# POE_PD_3_P-Schalter.net
KiCad netlist of a schematic drawn in EAGLE
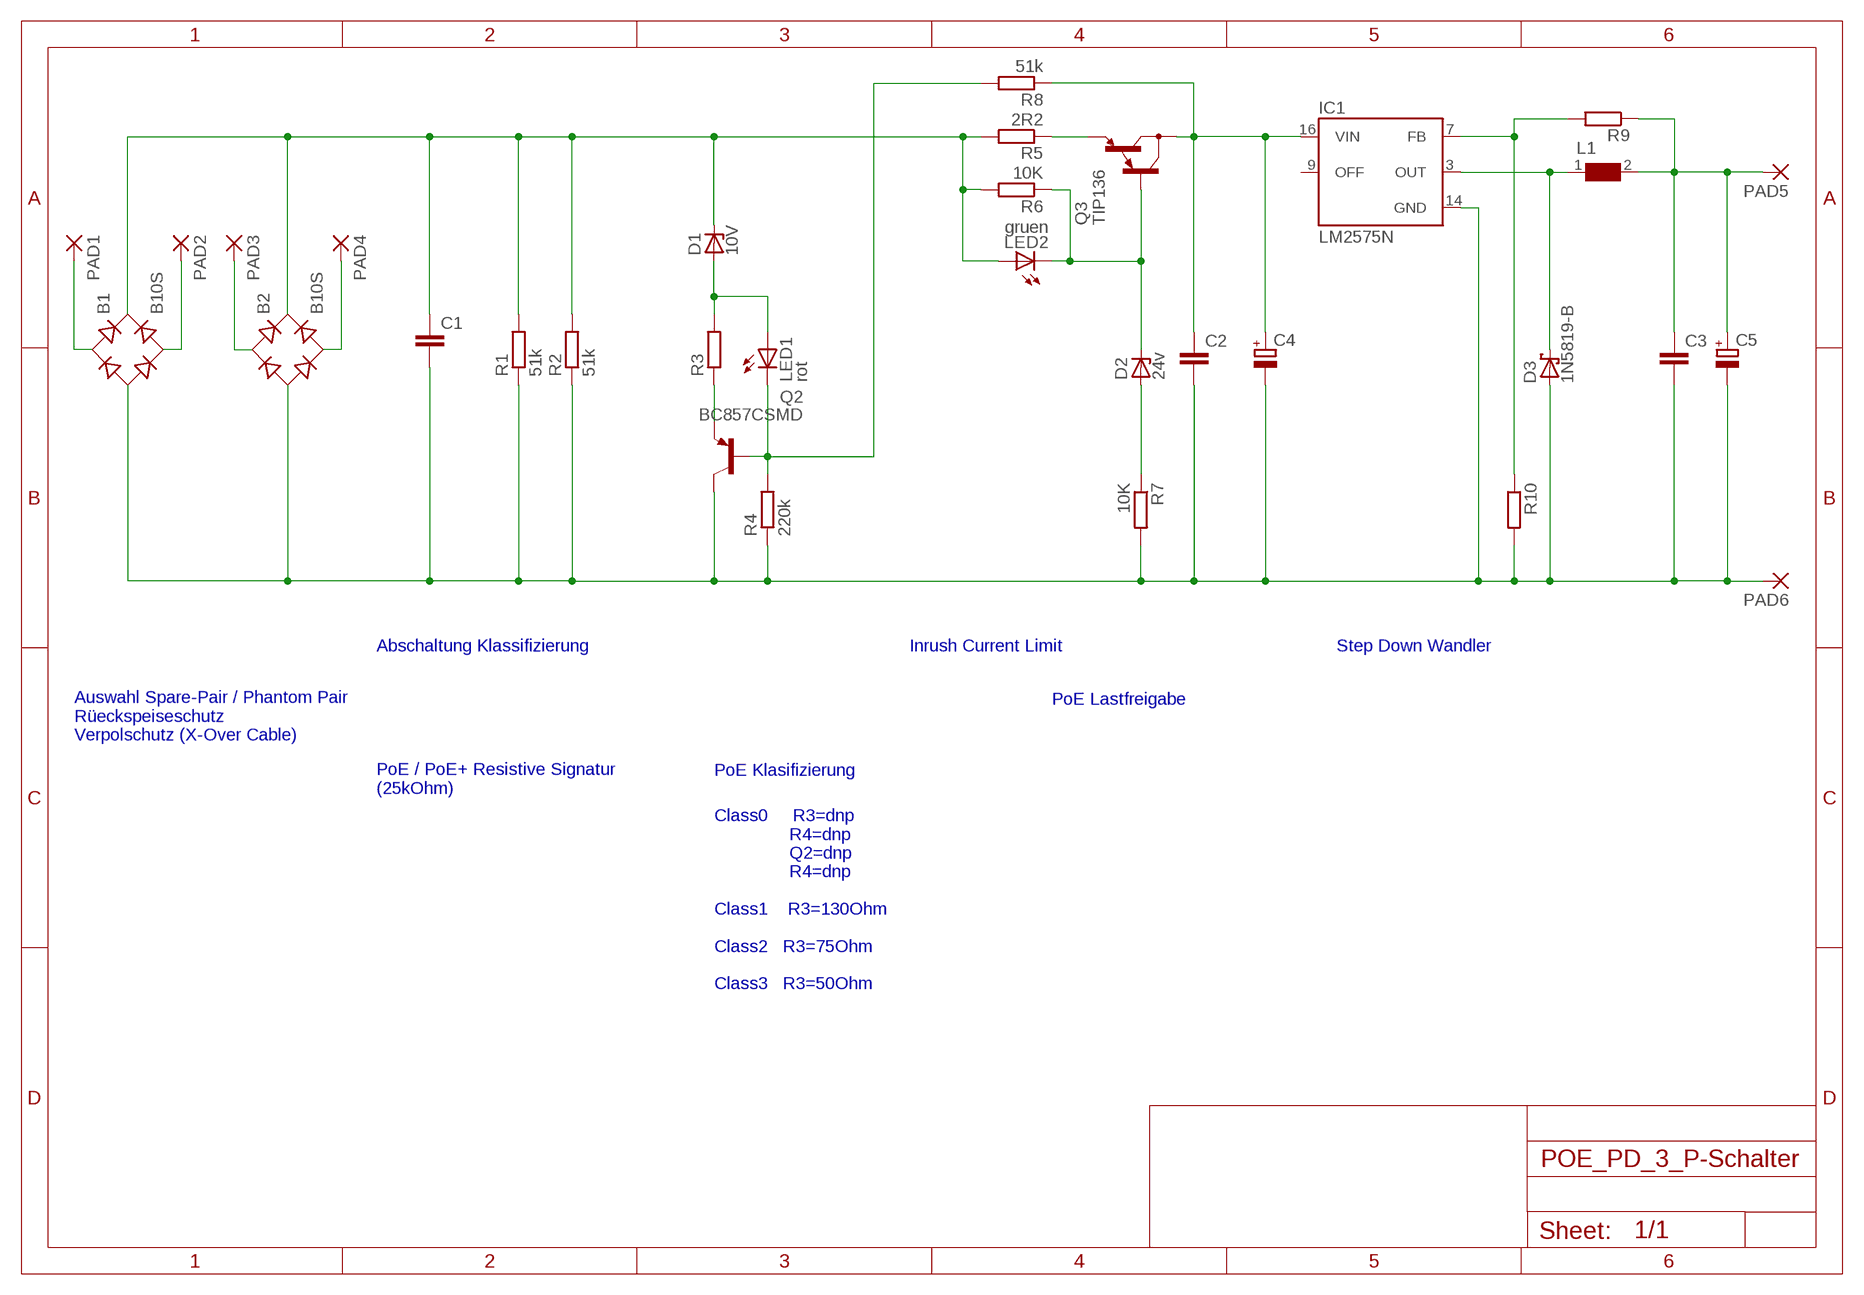
[diagram p0: schematic, sheet 1]

(export (version "E")
  (design (tool "Eeschema 10.0.6"))
  (components
    (comp (ref "B1")
      (value "B10S")
      (footprint "eagle-import:MBS")
      (libsource (lib "eagle-import") (part "BS10"))
    )
    (comp (ref "B2")
      (value "B10S")
      (footprint "eagle-import:MBS")
      (libsource (lib "eagle-import") (part "BS10"))
    )
    (comp (ref "C1")
      (value "C-EUC0805")
      (footprint "eagle-import:C0805")
      (libsource (lib "eagle-import") (part "C-EUC0805"))
    )
    (comp (ref "C2")
      (value "C-EUC0805")
      (footprint "eagle-import:C0805")
      (libsource (lib "eagle-import") (part "C-EUC0805"))
    )
    (comp (ref "C3")
      (value "C-EUC0805")
      (footprint "eagle-import:C0805")
      (libsource (lib "eagle-import") (part "C-EUC0805"))
    )
    (comp (ref "C4")
      (value "CPOL-EU153CLV-0605")
      (footprint "eagle-import:153CLV-0605")
      (libsource (lib "eagle-import") (part "CPOL-EU153CLV-0605"))
    )
    (comp (ref "C5")
      (value "CPOL-EU153CLV-0605")
      (footprint "eagle-import:153CLV-0605")
      (libsource (lib "eagle-import") (part "CPOL-EU153CLV-0605"))
    )
    (comp (ref "D1")
      (value "10V")
      (footprint "eagle-import:SOT23")
      (libsource (lib "eagle-import") (part "ZENER-DIODESOT23"))
    )
    (comp (ref "D2")
      (value "24v")
      (footprint "eagle-import:SOT23")
      (libsource (lib "eagle-import") (part "ZENER-DIODESOT23"))
    )
    (comp (ref "D3")
      (value "1N5819-B")
      (footprint "eagle-import:DO41-7.6")
      (libsource (lib "eagle-import") (part "1N5819-B"))
    )
    (comp (ref "IC1")
      (value "LM2575N")
      (footprint "eagle-import:DIL16")
      (libsource (lib "eagle-import") (part "LM2575N"))
    )
    (comp (ref "L1")
      (value "WE-PD2_S")
      (footprint "eagle-import:WE-PD2_S")
      (libsource (lib "eagle-import") (part "WE-PD2_S"))
    )
    (comp (ref "LED1")
      (value "rot")
      (footprint "eagle-import:CHIP-LED0805")
      (libsource (lib "eagle-import") (part "LEDCHIP-LED0805"))
    )
    (comp (ref "LED2")
      (value "gruen")
      (footprint "eagle-import:CHIP-LED0805")
      (libsource (lib "eagle-import") (part "LEDCHIP-LED0805"))
    )
    (comp (ref "PAD1")
      (value "2,15/1,0")
      (footprint "eagle-import:2,15_1,0")
      (libsource (lib "eagle-import") (part "2,15/1,0"))
    )
    (comp (ref "PAD2")
      (value "2,15/1,0")
      (footprint "eagle-import:2,15_1,0")
      (libsource (lib "eagle-import") (part "2,15/1,0"))
    )
    (comp (ref "PAD3")
      (value "2,15/1,0")
      (footprint "eagle-import:2,15_1,0")
      (libsource (lib "eagle-import") (part "2,15/1,0"))
    )
    (comp (ref "PAD4")
      (value "2,15/1,0")
      (footprint "eagle-import:2,15_1,0")
      (libsource (lib "eagle-import") (part "2,15/1,0"))
    )
    (comp (ref "PAD5")
      (value "2,15/1,0")
      (footprint "eagle-import:2,15_1,0")
      (libsource (lib "eagle-import") (part "2,15/1,0"))
    )
    (comp (ref "PAD6")
      (value "2,15/1,0")
      (footprint "eagle-import:2,15_1,0")
      (libsource (lib "eagle-import") (part "2,15/1,0"))
    )
    (comp (ref "Q2")
      (value "BC857CSMD")
      (footprint "eagle-import:SOT23-BEC")
      (libsource (lib "eagle-import") (part "BC857SMDC"))
    )
    (comp (ref "Q3")
      (value "TIP136")
      (footprint "eagle-import:TO220")
      (libsource (lib "eagle-import") (part "TIP136"))
    )
    (comp (ref "R1")
      (value "51k")
      (footprint "eagle-import:R0603")
      (libsource (lib "eagle-import") (part "R-EU_R0603"))
    )
    (comp (ref "R2")
      (value "51k")
      (footprint "eagle-import:R0603")
      (libsource (lib "eagle-import") (part "R-EU_R0603"))
    )
    (comp (ref "R3")
      (value "R-EU_R0603")
      (footprint "eagle-import:R0603")
      (libsource (lib "eagle-import") (part "R-EU_R0603"))
    )
    (comp (ref "R4")
      (value "220k")
      (footprint "eagle-import:R0603")
      (libsource (lib "eagle-import") (part "R-EU_R0603"))
    )
    (comp (ref "R5")
      (value "2R2")
      (footprint "eagle-import:R0603")
      (libsource (lib "eagle-import") (part "R-EU_R0603"))
    )
    (comp (ref "R6")
      (value "10K")
      (footprint "eagle-import:R0603")
      (libsource (lib "eagle-import") (part "R-EU_R0603"))
    )
    (comp (ref "R7")
      (value "10K")
      (footprint "eagle-import:R0603")
      (libsource (lib "eagle-import") (part "R-EU_R0603"))
    )
    (comp (ref "R8")
      (value "51k")
      (footprint "eagle-import:R0603")
      (libsource (lib "eagle-import") (part "R-EU_R0603"))
    )
    (comp (ref "R9")
      (value "R-EU_R0603")
      (footprint "eagle-import:R0603")
      (libsource (lib "eagle-import") (part "R-EU_R0603"))
    )
    (comp (ref "R10")
      (value "R-EU_R0603")
      (footprint "eagle-import:R0603")
      (libsource (lib "eagle-import") (part "R-EU_R0603"))
    )
  )
  (nets
    (net (code "1") (name "Net-(D1-A)") (class "Default")
      (node (ref "D1") (pin "1") (pinfunction "A_1") (pintype "passive"))
      (node (ref "LED1") (pin "A") (pinfunction "A_A") (pintype "passive"))
      (node (ref "R3") (pin "2") (pinfunction "2_2") (pintype "passive"))
    )
    (net (code "2") (name "Net-(D1-C)") (class "Default")
      (node (ref "B1") (pin "+") (pinfunction "+_+") (pintype "passive"))
      (node (ref "B2") (pin "+") (pinfunction "+_+") (pintype "passive"))
      (node (ref "C1") (pin "1") (pinfunction "1_1") (pintype "passive"))
      (node (ref "D1") (pin "3") (pinfunction "C_3") (pintype "passive"))
      (node (ref "LED2") (pin "A") (pinfunction "A_A") (pintype "passive"))
      (node (ref "R1") (pin "2") (pinfunction "2_2") (pintype "passive"))
      (node (ref "R2") (pin "2") (pinfunction "2_2") (pintype "passive"))
      (node (ref "R5") (pin "2") (pinfunction "2_2") (pintype "passive"))
      (node (ref "R6") (pin "2") (pinfunction "2_2") (pintype "passive"))
    )
    (net (code "3") (name "Net-(D2-A)") (class "Default")
      (node (ref "D2") (pin "1") (pinfunction "A_1") (pintype "passive"))
      (node (ref "R7") (pin "1") (pinfunction "1_1") (pintype "passive"))
    )
    (net (code "4") (name "Net-(D2-C)") (class "Default")
      (node (ref "D2") (pin "3") (pinfunction "C_3") (pintype "passive"))
      (node (ref "LED2") (pin "C") (pinfunction "C_C") (pintype "passive"))
      (node (ref "Q3") (pin "1") (pinfunction "B_1") (pintype "passive"))
      (node (ref "R6") (pin "1") (pinfunction "1_1") (pintype "passive"))
    )
    (net (code "5") (name "Net-(IC1-FB)") (class "Default")
      (node (ref "IC1") (pin "7") (pinfunction "FB_7") (pintype "input"))
      (node (ref "R10") (pin "1") (pinfunction "1_1") (pintype "passive"))
      (node (ref "R9") (pin "2") (pinfunction "2_2") (pintype "passive"))
    )
    (net (code "6") (name "Net-(IC1-GND)") (class "Default")
      (node (ref "B1") (pin "-") (pinfunction "-_-") (pintype "passive"))
      (node (ref "B2") (pin "-") (pinfunction "-_-") (pintype "passive"))
      (node (ref "C1") (pin "2") (pinfunction "2_2") (pintype "passive"))
      (node (ref "C2") (pin "2") (pinfunction "2_2") (pintype "passive"))
      (node (ref "C3") (pin "2") (pinfunction "2_2") (pintype "passive"))
      (node (ref "C4") (pin "-") (pinfunction "-_-") (pintype "passive"))
      (node (ref "C5") (pin "-") (pinfunction "-_-") (pintype "passive"))
      (node (ref "D3") (pin "A") (pinfunction "A_A") (pintype "passive"))
      (node (ref "IC1") (pin "14") (pinfunction "GND_14") (pintype "power_in"))
      (node (ref "PAD6") (pin "1") (pinfunction "P_1") (pintype "passive"))
      (node (ref "Q2") (pin "C") (pinfunction "C_C") (pintype "passive"))
      (node (ref "R1") (pin "1") (pinfunction "1_1") (pintype "passive"))
      (node (ref "R10") (pin "2") (pinfunction "2_2") (pintype "passive"))
      (node (ref "R2") (pin "1") (pinfunction "1_1") (pintype "passive"))
      (node (ref "R4") (pin "1") (pinfunction "1_1") (pintype "passive"))
      (node (ref "R7") (pin "2") (pinfunction "2_2") (pintype "passive"))
    )
    (net (code "7") (name "Net-(IC1-OUT)") (class "Default")
      (node (ref "D3") (pin "C") (pinfunction "C_C") (pintype "passive"))
      (node (ref "IC1") (pin "3") (pinfunction "OUT_3") (pintype "output"))
      (node (ref "L1") (pin "1") (pinfunction "1_1") (pintype "passive"))
    )
    (net (code "8") (name "Net-(IC1-VIN)") (class "Default")
      (node (ref "C2") (pin "1") (pinfunction "1_1") (pintype "passive"))
      (node (ref "C4") (pin "+") (pinfunction "+_+") (pintype "passive"))
      (node (ref "IC1") (pin "16") (pinfunction "VIN_16") (pintype "power_in"))
      (node (ref "Q3") (pin "2") (pinfunction "C_2") (pintype "passive"))
      (node (ref "R8") (pin "1") (pinfunction "1_1") (pintype "passive"))
    )
    (net (code "9") (name "Net-(LED1-PadC)") (class "Default")
      (node (ref "LED1") (pin "C") (pinfunction "C_C") (pintype "passive"))
      (node (ref "Q2") (pin "B") (pinfunction "B_B") (pintype "passive"))
      (node (ref "R4") (pin "2") (pinfunction "2_2") (pintype "passive"))
      (node (ref "R8") (pin "2") (pinfunction "2_2") (pintype "passive"))
    )
    (net (code "10") (name "Net-(PAD1-P)") (class "Default")
      (node (ref "B1") (pin "AC1") (pinfunction "AC1_AC1") (pintype "passive"))
      (node (ref "PAD1") (pin "1") (pinfunction "P_1") (pintype "passive"))
    )
    (net (code "11") (name "Net-(PAD2-P)") (class "Default")
      (node (ref "B1") (pin "AC2") (pinfunction "AC2_AC2") (pintype "passive"))
      (node (ref "PAD2") (pin "1") (pinfunction "P_1") (pintype "passive"))
    )
    (net (code "12") (name "Net-(PAD3-P)") (class "Default")
      (node (ref "B2") (pin "AC1") (pinfunction "AC1_AC1") (pintype "passive"))
      (node (ref "PAD3") (pin "1") (pinfunction "P_1") (pintype "passive"))
    )
    (net (code "13") (name "Net-(PAD4-P)") (class "Default")
      (node (ref "B2") (pin "AC2") (pinfunction "AC2_AC2") (pintype "passive"))
      (node (ref "PAD4") (pin "1") (pinfunction "P_1") (pintype "passive"))
    )
    (net (code "14") (name "Net-(PAD5-P)") (class "Default")
      (node (ref "C3") (pin "1") (pinfunction "1_1") (pintype "passive"))
      (node (ref "C5") (pin "+") (pinfunction "+_+") (pintype "passive"))
      (node (ref "L1") (pin "2") (pinfunction "2_2") (pintype "passive"))
      (node (ref "PAD5") (pin "1") (pinfunction "P_1") (pintype "passive"))
      (node (ref "R9") (pin "1") (pinfunction "1_1") (pintype "passive"))
    )
    (net (code "15") (name "Net-(Q2-PadE)") (class "Default")
      (node (ref "Q2") (pin "E") (pinfunction "E_E") (pintype "passive"))
      (node (ref "R3") (pin "1") (pinfunction "1_1") (pintype "passive"))
    )
    (net (code "16") (name "Net-(Q3-E)") (class "Default")
      (node (ref "Q3") (pin "3") (pinfunction "E_3") (pintype "passive"))
      (node (ref "R5") (pin "1") (pinfunction "1_1") (pintype "passive"))
    )
    (net (code "17") (name "unconnected-(IC1-OFF-Pad9)") (class "Default")
      (node (ref "IC1") (pin "9") (pinfunction "OFF_9") (pintype "input"))
    )
  )
)
